# encoder.net
KiCad netlist of a schematic drawn in EAGLE
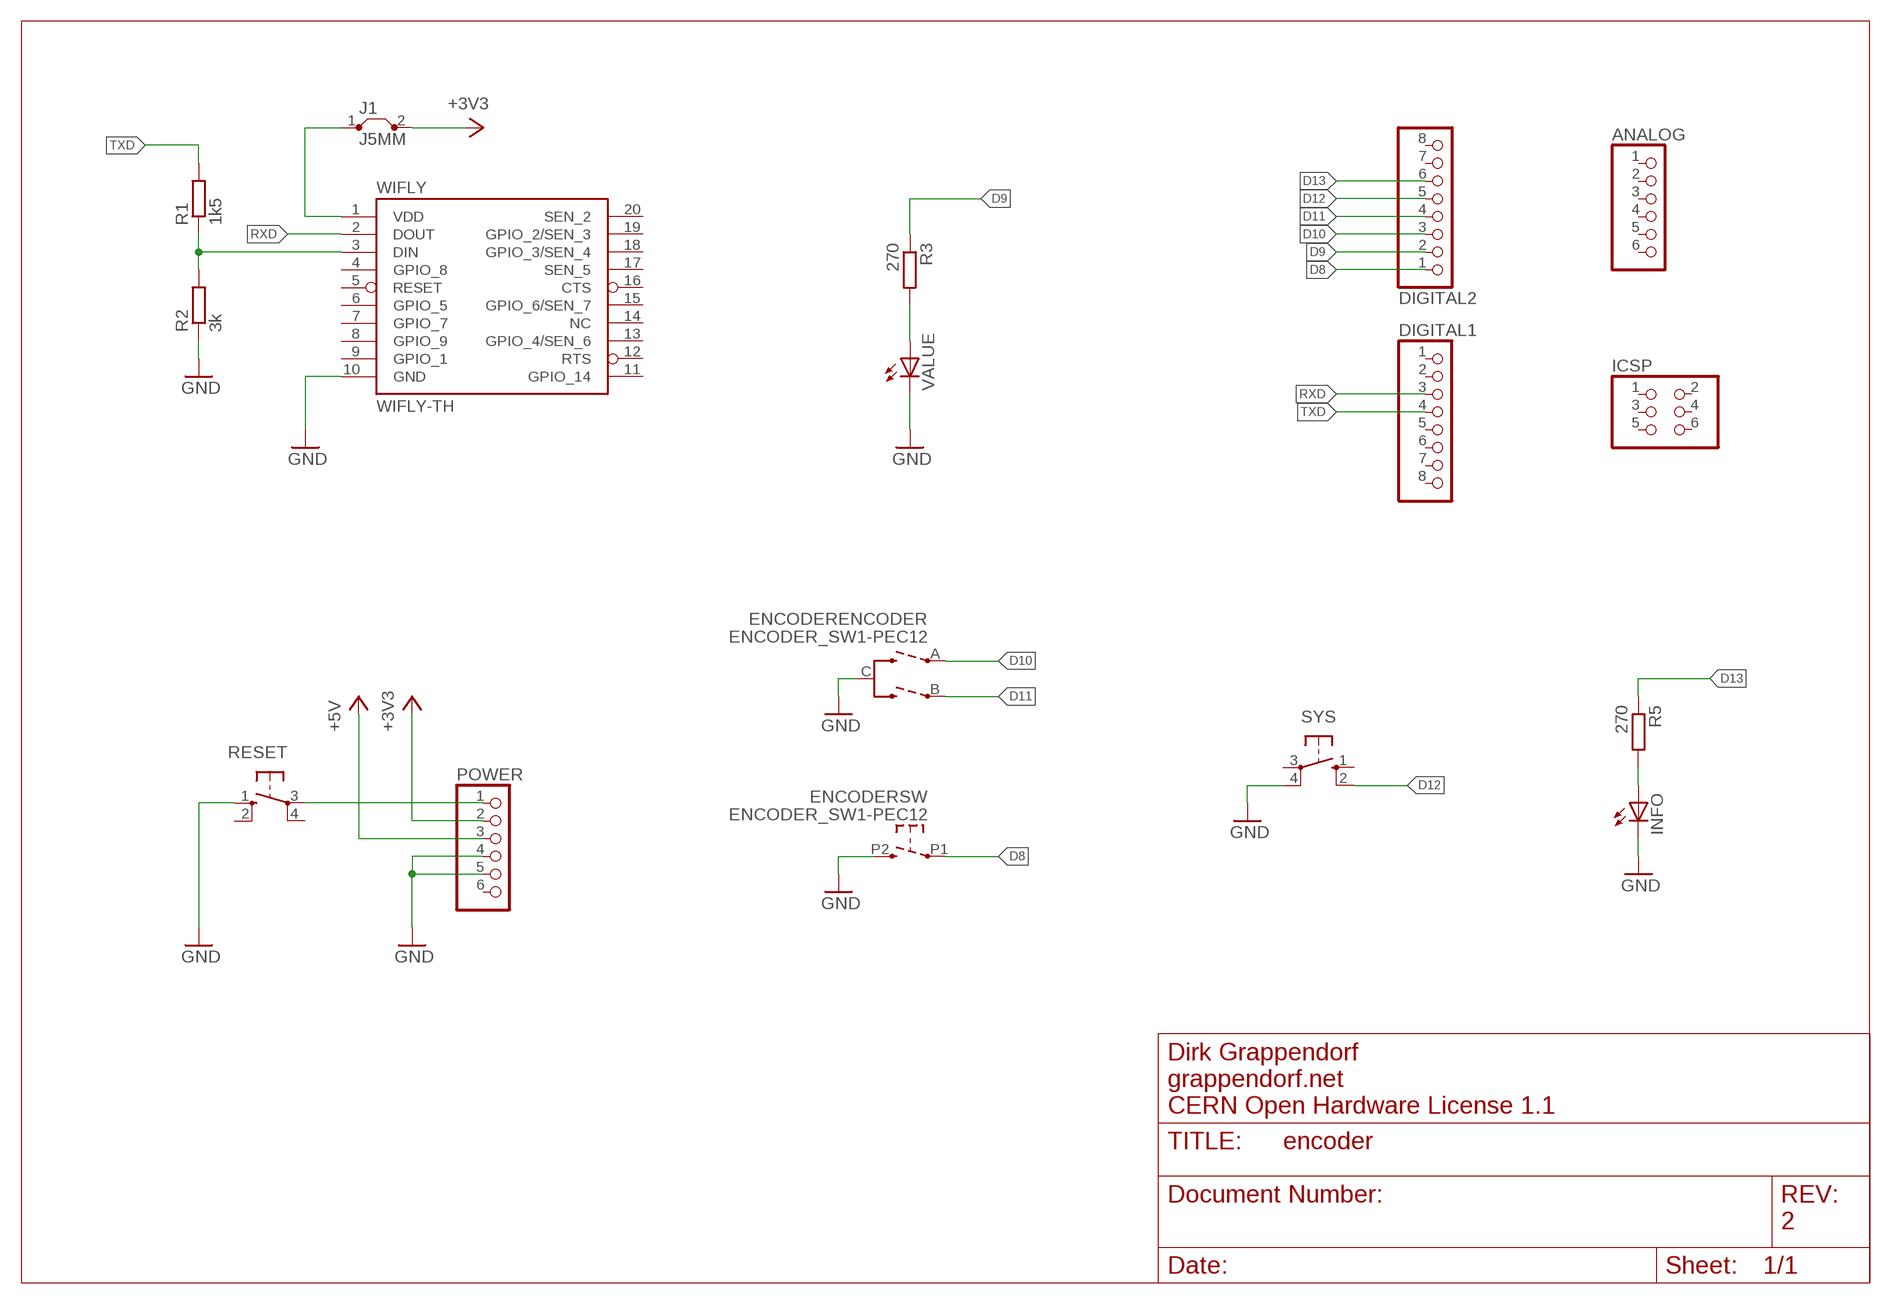
[diagram p0: schematic, sheet 1]

(export (version "E")
  (design (tool "Eeschema 10.0.6"))
  (components
    (comp (ref "ANALOG")
      (value "PINHD-1X6")
      (footprint "eagle-import:1X06")
      (libsource (lib "eagle-import") (part "PINHD-1X6"))
    )
    (comp (ref "DIGITAL1")
      (value "PINHD-1X8TH")
      (footprint "eagle-import:1X08-TH")
      (libsource (lib "eagle-import") (part "PINHD-1X8TH"))
    )
    (comp (ref "DIGITAL2")
      (value "PINHD-1X8_2.54")
      (footprint "eagle-import:1X08")
      (libsource (lib "eagle-import") (part "PINHD-1X8_2.54"))
    )
    (comp (ref "ENCODER")
      (value "ENCODER_SW1-PEC12")
      (footprint "eagle-import:PEC12_INCREMENTAL_ENCODER")
      (libsource (lib "eagle-import") (part "ENCODER_SW1-PEC12"))
    )
    (comp (ref "ICSP")
      (value "PINHD-2X3")
      (footprint "eagle-import:2X03")
      (libsource (lib "eagle-import") (part "PINHD-2X3"))
    )
    (comp (ref "INFO")
      (value "LED3MM")
      (footprint "eagle-import:LED3MM")
      (libsource (lib "eagle-import") (part "LED3MM"))
    )
    (comp (ref "J1")
      (value "J5MM")
      (footprint "eagle-import:05")
      (libsource (lib "eagle-import") (part "J5MM"))
    )
    (comp (ref "POWER")
      (value "PINHD-1X6_2.54")
      (footprint "eagle-import:1X06")
      (libsource (lib "eagle-import") (part "PINHD-1X6_2.54"))
    )
    (comp (ref "R1")
      (value "1k5")
      (footprint "eagle-import:0204_7")
      (libsource (lib "eagle-import") (part "R-EU_0204/7"))
    )
    (comp (ref "R2")
      (value "3k")
      (footprint "eagle-import:0204_7")
      (libsource (lib "eagle-import") (part "R-EU_0204/7"))
    )
    (comp (ref "R3")
      (value "270")
      (footprint "eagle-import:0204_7")
      (libsource (lib "eagle-import") (part "R-EU_0204/7"))
    )
    (comp (ref "R5")
      (value "270")
      (footprint "eagle-import:0204_7")
      (libsource (lib "eagle-import") (part "R-EU_0204/7"))
    )
    (comp (ref "RESET")
      (value "10-XX")
      (footprint "eagle-import:B3F-10XX")
      (libsource (lib "eagle-import") (part "10-XX"))
    )
    (comp (ref "SYS")
      (value "10-XX")
      (footprint "eagle-import:B3F-10XX")
      (libsource (lib "eagle-import") (part "10-XX"))
    )
    (comp (ref "VALUE")
      (value "LED3MM")
      (footprint "eagle-import:LED3MM")
      (libsource (lib "eagle-import") (part "LED3MM"))
    )
    (comp (ref "WIFLY")
      (value "WIFLY-TH")
      (footprint "eagle-import:WIFLY-TH")
      (libsource (lib "eagle-import") (part "WIFLY-TH"))
    )
  )
  (nets
    (net (code "1") (name "+3V3") (class "Default")
      (node (ref "J1") (pin "2") (pinfunction "2_2") (pintype "passive"))
      (node (ref "POWER") (pin "2") (pinfunction "2_2") (pintype "passive"))
    )
    (net (code "2") (name "+5V") (class "Default")
      (node (ref "POWER") (pin "3") (pinfunction "3_3") (pintype "passive"))
    )
    (net (code "3") (name "D8") (class "Default")
      (node (ref "DIGITAL2") (pin "1") (pinfunction "1_1") (pintype "passive"))
      (node (ref "ENCODER") (pin "P1") (pinfunction "1_P1") (pintype "passive"))
    )
    (net (code "4") (name "D9") (class "Default")
      (node (ref "DIGITAL2") (pin "2") (pinfunction "2_2") (pintype "passive"))
      (node (ref "R3") (pin "1") (pinfunction "1_1") (pintype "passive"))
    )
    (net (code "5") (name "D10") (class "Default")
      (node (ref "DIGITAL2") (pin "3") (pinfunction "3_3") (pintype "passive"))
      (node (ref "ENCODER") (pin "A") (pinfunction "A_A") (pintype "passive"))
    )
    (net (code "6") (name "D11") (class "Default")
      (node (ref "DIGITAL2") (pin "4") (pinfunction "4_4") (pintype "passive"))
      (node (ref "ENCODER") (pin "B") (pinfunction "B_B") (pintype "passive"))
    )
    (net (code "7") (name "D12") (class "Default")
      (node (ref "DIGITAL2") (pin "5") (pinfunction "5_5") (pintype "passive"))
      (node (ref "SYS") (pin "2") (pinfunction "S1_2") (pintype "passive"))
    )
    (net (code "8") (name "D13") (class "Default")
      (node (ref "DIGITAL2") (pin "6") (pinfunction "6_6") (pintype "passive"))
      (node (ref "R5") (pin "1") (pinfunction "1_1") (pintype "passive"))
    )
    (net (code "9") (name "GND") (class "Default")
      (node (ref "ENCODER") (pin "C") (pinfunction "C_C") (pintype "passive"))
      (node (ref "ENCODER") (pin "P2") (pinfunction "2_P2") (pintype "passive"))
      (node (ref "INFO") (pin "K") (pinfunction "C_K") (pintype "passive"))
      (node (ref "POWER") (pin "4") (pinfunction "4_4") (pintype "passive"))
      (node (ref "POWER") (pin "5") (pinfunction "5_5") (pintype "passive"))
      (node (ref "R2") (pin "1") (pinfunction "1_1") (pintype "passive"))
      (node (ref "RESET") (pin "1") (pinfunction "S_1") (pintype "passive"))
      (node (ref "SYS") (pin "4") (pinfunction "P1_4") (pintype "passive"))
      (node (ref "VALUE") (pin "K") (pinfunction "C_K") (pintype "passive"))
      (node (ref "WIFLY") (pin "10") (pinfunction "GND_10") (pintype "power_in"))
    )
    (net (code "10") (name "Net-(INFO-PadA)") (class "Default")
      (node (ref "INFO") (pin "A") (pinfunction "A_A") (pintype "passive"))
      (node (ref "R5") (pin "2") (pinfunction "2_2") (pintype "passive"))
    )
    (net (code "11") (name "Net-(R3-Pad2)") (class "Default")
      (node (ref "R3") (pin "2") (pinfunction "2_2") (pintype "passive"))
      (node (ref "VALUE") (pin "A") (pinfunction "A_A") (pintype "passive"))
    )
    (net (code "12") (name "Net-(RESET-P)") (class "Default")
      (node (ref "POWER") (pin "1") (pinfunction "1_1") (pintype "passive"))
      (node (ref "RESET") (pin "3") (pinfunction "P_3") (pintype "passive"))
    )
    (net (code "13") (name "Net-(WIFLY-DIN)") (class "Default")
      (node (ref "R1") (pin "1") (pinfunction "1_1") (pintype "passive"))
      (node (ref "R2") (pin "2") (pinfunction "2_2") (pintype "passive"))
      (node (ref "WIFLY") (pin "3") (pinfunction "DIN_3") (pintype "input"))
    )
    (net (code "14") (name "Net-(WIFLY-VDD)") (class "Default")
      (node (ref "J1") (pin "1") (pinfunction "1_1") (pintype "passive"))
      (node (ref "WIFLY") (pin "1") (pinfunction "VDD_1") (pintype "power_in"))
    )
    (net (code "15") (name "RXD") (class "Default")
      (node (ref "DIGITAL1") (pin "3") (pinfunction "3_3") (pintype "passive"))
      (node (ref "WIFLY") (pin "2") (pinfunction "DOUT_2") (pintype "output"))
    )
    (net (code "16") (name "TXD") (class "Default")
      (node (ref "DIGITAL1") (pin "4") (pinfunction "4_4") (pintype "passive"))
      (node (ref "R1") (pin "2") (pinfunction "2_2") (pintype "passive"))
    )
    (net (code "17") (name "unconnected-(ANALOG-Pad1)") (class "Default")
      (node (ref "ANALOG") (pin "1") (pinfunction "1_1") (pintype "passive"))
    )
    (net (code "18") (name "unconnected-(ANALOG-Pad2)") (class "Default")
      (node (ref "ANALOG") (pin "2") (pinfunction "2_2") (pintype "passive"))
    )
    (net (code "19") (name "unconnected-(ANALOG-Pad3)") (class "Default")
      (node (ref "ANALOG") (pin "3") (pinfunction "3_3") (pintype "passive"))
    )
    (net (code "20") (name "unconnected-(ANALOG-Pad4)") (class "Default")
      (node (ref "ANALOG") (pin "4") (pinfunction "4_4") (pintype "passive"))
    )
    (net (code "21") (name "unconnected-(ANALOG-Pad5)") (class "Default")
      (node (ref "ANALOG") (pin "5") (pinfunction "5_5") (pintype "passive"))
    )
    (net (code "22") (name "unconnected-(ANALOG-Pad6)") (class "Default")
      (node (ref "ANALOG") (pin "6") (pinfunction "6_6") (pintype "passive"))
    )
    (net (code "23") (name "unconnected-(DIGITAL1-Pad1)") (class "Default")
      (node (ref "DIGITAL1") (pin "1") (pinfunction "1_1") (pintype "passive"))
    )
    (net (code "24") (name "unconnected-(DIGITAL1-Pad2)") (class "Default")
      (node (ref "DIGITAL1") (pin "2") (pinfunction "2_2") (pintype "passive"))
    )
    (net (code "25") (name "unconnected-(DIGITAL1-Pad5)") (class "Default")
      (node (ref "DIGITAL1") (pin "5") (pinfunction "5_5") (pintype "passive"))
    )
    (net (code "26") (name "unconnected-(DIGITAL1-Pad6)") (class "Default")
      (node (ref "DIGITAL1") (pin "6") (pinfunction "6_6") (pintype "passive"))
    )
    (net (code "27") (name "unconnected-(DIGITAL1-Pad7)") (class "Default")
      (node (ref "DIGITAL1") (pin "7") (pinfunction "7_7") (pintype "passive"))
    )
    (net (code "28") (name "unconnected-(DIGITAL1-Pad8)") (class "Default")
      (node (ref "DIGITAL1") (pin "8") (pinfunction "8_8") (pintype "passive"))
    )
    (net (code "29") (name "unconnected-(DIGITAL2-Pad7)") (class "Default")
      (node (ref "DIGITAL2") (pin "7") (pinfunction "7_7") (pintype "passive"))
    )
    (net (code "30") (name "unconnected-(DIGITAL2-Pad8)") (class "Default")
      (node (ref "DIGITAL2") (pin "8") (pinfunction "8_8") (pintype "passive"))
    )
    (net (code "31") (name "unconnected-(ICSP-Pad1)") (class "Default")
      (node (ref "ICSP") (pin "1") (pinfunction "1_1") (pintype "passive"))
    )
    (net (code "32") (name "unconnected-(ICSP-Pad2)") (class "Default")
      (node (ref "ICSP") (pin "2") (pinfunction "2_2") (pintype "passive"))
    )
    (net (code "33") (name "unconnected-(ICSP-Pad3)") (class "Default")
      (node (ref "ICSP") (pin "3") (pinfunction "3_3") (pintype "passive"))
    )
    (net (code "34") (name "unconnected-(ICSP-Pad4)") (class "Default")
      (node (ref "ICSP") (pin "4") (pinfunction "4_4") (pintype "passive"))
    )
    (net (code "35") (name "unconnected-(ICSP-Pad5)") (class "Default")
      (node (ref "ICSP") (pin "5") (pinfunction "5_5") (pintype "passive"))
    )
    (net (code "36") (name "unconnected-(ICSP-Pad6)") (class "Default")
      (node (ref "ICSP") (pin "6") (pinfunction "6_6") (pintype "passive"))
    )
    (net (code "37") (name "unconnected-(POWER-Pad6)") (class "Default")
      (node (ref "POWER") (pin "6") (pinfunction "6_6") (pintype "passive"))
    )
    (net (code "38") (name "unconnected-(RESET-P1-Pad4)") (class "Default")
      (node (ref "RESET") (pin "4") (pinfunction "P1_4") (pintype "passive"))
    )
    (net (code "39") (name "unconnected-(RESET-S1-Pad2)") (class "Default")
      (node (ref "RESET") (pin "2") (pinfunction "S1_2") (pintype "passive"))
    )
    (net (code "40") (name "unconnected-(SYS-P-Pad3)") (class "Default")
      (node (ref "SYS") (pin "3") (pinfunction "P_3") (pintype "passive"))
    )
    (net (code "41") (name "unconnected-(SYS-S-Pad1)") (class "Default")
      (node (ref "SYS") (pin "1") (pinfunction "S_1") (pintype "passive"))
    )
    (net (code "42") (name "unconnected-(WIFLY-CTS-Pad16)") (class "Default")
      (node (ref "WIFLY") (pin "16") (pinfunction "CTS_16") (pintype "input"))
    )
    (net (code "43") (name "unconnected-(WIFLY-GPIO_1-Pad9)") (class "Default")
      (node (ref "WIFLY") (pin "9") (pinfunction "GPIO_1_9") (pintype "bidirectional"))
    )
    (net (code "44") (name "unconnected-(WIFLY-GPIO_2{slash}SEN_3-Pad19)") (class "Default")
      (node (ref "WIFLY") (pin "19") (pinfunction "GPIO_2/SEN_3_19") (pintype "bidirectional"))
    )
    (net (code "45") (name "unconnected-(WIFLY-GPIO_3{slash}SEN_4-Pad18)") (class "Default")
      (node (ref "WIFLY") (pin "18") (pinfunction "GPIO_3/SEN_4_18") (pintype "bidirectional"))
    )
    (net (code "46") (name "unconnected-(WIFLY-GPIO_4{slash}SEN_6-Pad13)") (class "Default")
      (node (ref "WIFLY") (pin "13") (pinfunction "GPIO_4/SEN_6_13") (pintype "bidirectional"))
    )
    (net (code "47") (name "unconnected-(WIFLY-GPIO_5-Pad6)") (class "Default")
      (node (ref "WIFLY") (pin "6") (pinfunction "GPIO_5_6") (pintype "bidirectional"))
    )
    (net (code "48") (name "unconnected-(WIFLY-GPIO_6{slash}SEN_7-Pad15)") (class "Default")
      (node (ref "WIFLY") (pin "15") (pinfunction "GPIO_6/SEN_7_15") (pintype "bidirectional"))
    )
    (net (code "49") (name "unconnected-(WIFLY-GPIO_7-Pad7)") (class "Default")
      (node (ref "WIFLY") (pin "7") (pinfunction "GPIO_7_7") (pintype "bidirectional"))
    )
    (net (code "50") (name "unconnected-(WIFLY-GPIO_8-Pad4)") (class "Default")
      (node (ref "WIFLY") (pin "4") (pinfunction "GPIO_8_4") (pintype "bidirectional"))
    )
    (net (code "51") (name "unconnected-(WIFLY-GPIO_9-Pad8)") (class "Default")
      (node (ref "WIFLY") (pin "8") (pinfunction "GPIO_9_8") (pintype "bidirectional"))
    )
    (net (code "52") (name "unconnected-(WIFLY-GPIO_14-Pad11)") (class "Default")
      (node (ref "WIFLY") (pin "11") (pinfunction "GPIO_14_11") (pintype "bidirectional"))
    )
    (net (code "53") (name "unconnected-(WIFLY-NC-Pad14)") (class "Default")
      (node (ref "WIFLY") (pin "14") (pinfunction "NC_14") (pintype "bidirectional"))
    )
    (net (code "54") (name "unconnected-(WIFLY-RESET-Pad5)") (class "Default")
      (node (ref "WIFLY") (pin "5") (pinfunction "RESET_5") (pintype "input"))
    )
    (net (code "55") (name "unconnected-(WIFLY-RTS-Pad12)") (class "Default")
      (node (ref "WIFLY") (pin "12") (pinfunction "RTS_12") (pintype "output"))
    )
    (net (code "56") (name "unconnected-(WIFLY-SEN_2-Pad20)") (class "Default")
      (node (ref "WIFLY") (pin "20") (pinfunction "SEN_2_20") (pintype "bidirectional"))
    )
    (net (code "57") (name "unconnected-(WIFLY-SEN_5-Pad17)") (class "Default")
      (node (ref "WIFLY") (pin "17") (pinfunction "SEN_5_17") (pintype "bidirectional"))
    )
  )
)
